# afficheur.net
KiCad netlist of a schematic drawn in Altium Designer
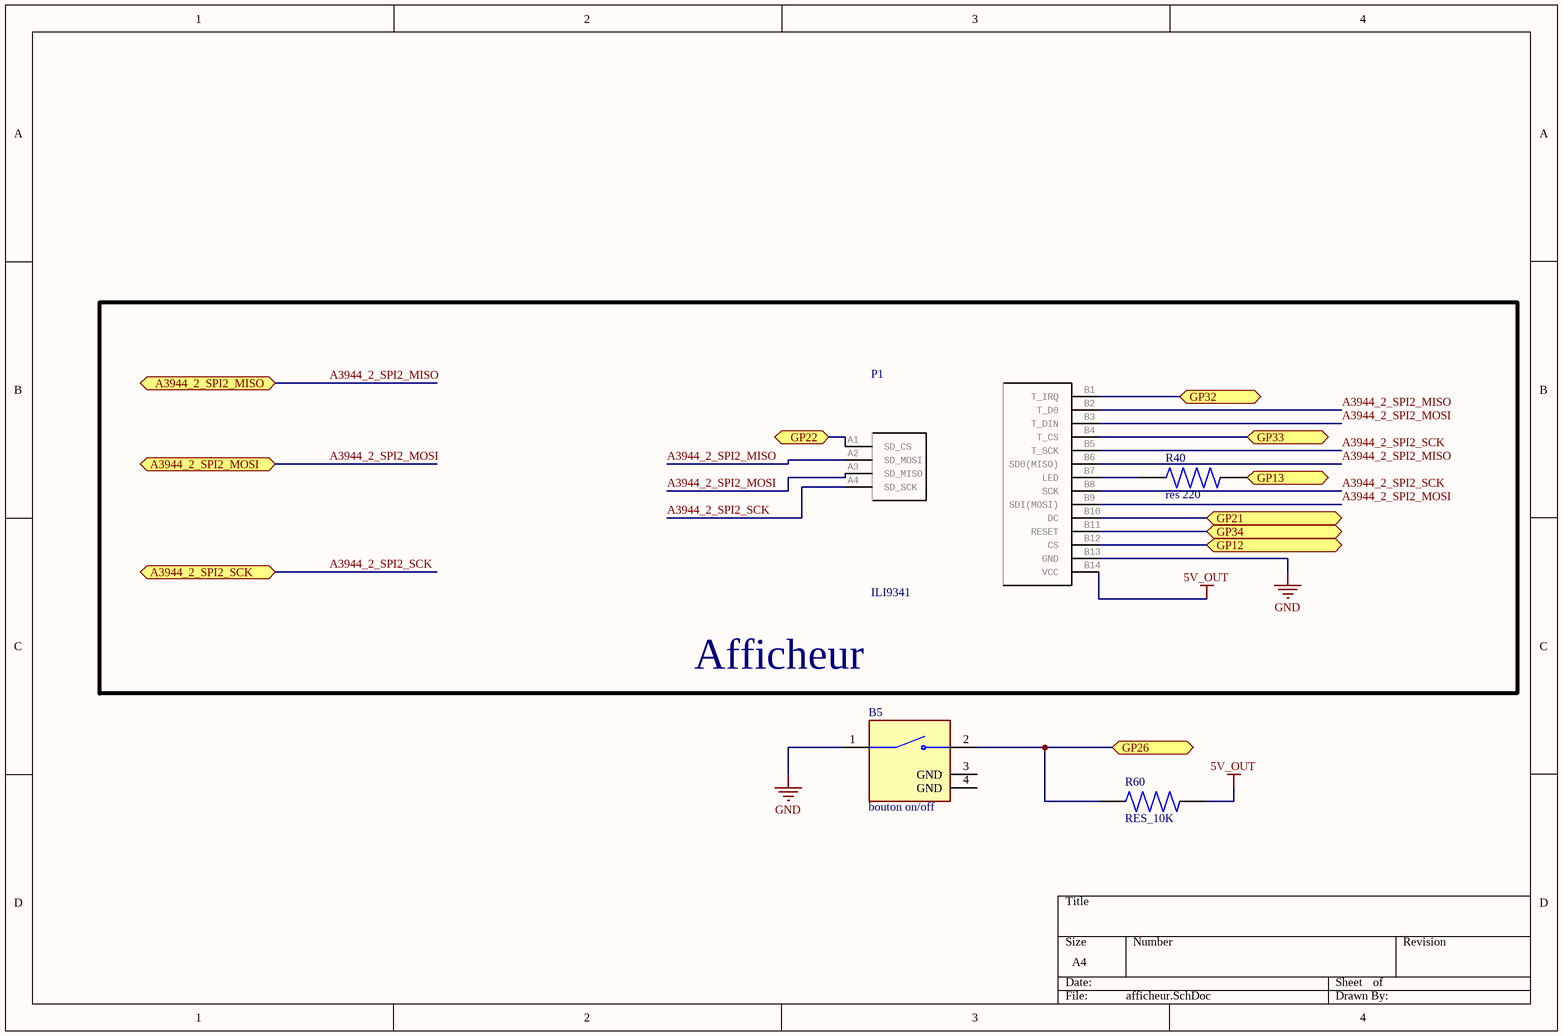
[diagram p0: afficheur.SchDoc]

(export (version "E")
  (design (tool "Eeschema 10.0.6"))
  (components
    (comp (ref "B5")
      (value "bouton on/off")
      (footprint "button")
      (fields (field (name "MFR") "CUI Devices"))
      (libsource (lib "Data_logger") (part "bouton reset"))
    )
    (comp (ref "P1") (value "ILI9341") (footprint "ILI9341") (libsource (lib "Data_logger") (part "ILI9341")))
    (comp (ref "R40")
      (value "res 220")
      (footprint "res 220")
      (libsource (lib "Data_logger") (part "res 220"))
    )
    (comp (ref "R60")
      (value "RES_10K")
      (footprint "RES_10k")
      (description "Thick Film Resistors - SMD ResHighPowerA 0805 10k 1% 1/2W TC100")
      (fields (field (name "MFR") "Bourns Inc."))
      (libsource (lib "Data_logger") (part "RES_10K"))
    )
  )
  (nets
    (net (code "1") (name "/A3944_2_SPI2_MISO") (class "Default")
      (node (ref "P1") (pin "A2") (pinfunction "SD_MOSI_A2") (pintype "passive"))
      (node (ref "P1") (pin "B2") (pinfunction "T_D0_B2") (pintype "passive"))
      (node (ref "P1") (pin "B6") (pinfunction "SD0(MISO)_B6") (pintype "passive"))
    )
    (net (code "2") (name "/A3944_2_SPI2_MOSI") (class "Default")
      (node (ref "P1") (pin "A3") (pinfunction "SD_MISO_A3") (pintype "passive"))
      (node (ref "P1") (pin "B3") (pinfunction "T_DIN_B3") (pintype "passive"))
      (node (ref "P1") (pin "B9") (pinfunction "SDI(MOSI)_B9") (pintype "passive"))
    )
    (net (code "3") (name "/A3944_2_SPI2_SCK") (class "Default")
      (node (ref "P1") (pin "A4") (pinfunction "SD_SCK_A4") (pintype "passive"))
      (node (ref "P1") (pin "B5") (pinfunction "T_SCK_B5") (pintype "passive"))
      (node (ref "P1") (pin "B8") (pinfunction "SCK_B8") (pintype "passive"))
    )
    (net (code "4") (name "/GP12") (class "Default")
      (node (ref "P1") (pin "B12") (pinfunction "CS_B12") (pintype "passive"))
    )
    (net (code "5") (name "/GP13") (class "Default")
      (node (ref "R40") (pin "2") (pinfunction "2_2") (pintype "passive"))
    )
    (net (code "6") (name "/GP21") (class "Default")
      (node (ref "P1") (pin "B10") (pinfunction "DC_B10") (pintype "passive"))
    )
    (net (code "7") (name "/GP22") (class "Default")
      (node (ref "P1") (pin "A1") (pinfunction "SD_CS_A1") (pintype "passive"))
    )
    (net (code "8") (name "/GP26") (class "Default")
      (node (ref "B5") (pin "2") (pinfunction "NO_2") (pintype "passive"))
      (node (ref "R60") (pin "1") (pinfunction "1_1") (pintype "passive"))
    )
    (net (code "9") (name "/GP32") (class "Default")
      (node (ref "P1") (pin "B1") (pinfunction "T_IRQ_B1") (pintype "passive"))
    )
    (net (code "10") (name "/GP33") (class "Default")
      (node (ref "P1") (pin "B4") (pinfunction "T_CS_B4") (pintype "passive"))
    )
    (net (code "11") (name "/GP34") (class "Default")
      (node (ref "P1") (pin "B11") (pinfunction "RESET_B11") (pintype "passive"))
    )
    (net (code "12") (name "5V_OUT") (class "Default")
      (node (ref "P1") (pin "B14") (pinfunction "VCC_B14") (pintype "passive"))
      (node (ref "R60") (pin "2") (pinfunction "2_2") (pintype "passive"))
    )
    (net (code "13") (name "GND") (class "Default")
      (node (ref "B5") (pin "1") (pinfunction "COM_1") (pintype "passive"))
      (node (ref "P1") (pin "B13") (pinfunction "GND_B13") (pintype "passive"))
    )
    (net (code "14") (name "Net-(P1-LED)") (class "Default")
      (node (ref "P1") (pin "B7") (pinfunction "LED_B7") (pintype "passive"))
      (node (ref "R40") (pin "1") (pinfunction "1_1") (pintype "passive"))
    )
    (net (code "15") (name "unconnected-(B5-GND-Pad3)") (class "Default")
      (node (ref "B5") (pin "3") (pinfunction "GND_3") (pintype "power_in"))
    )
    (net (code "16") (name "unconnected-(B5-GND-Pad4)") (class "Default")
      (node (ref "B5") (pin "4") (pinfunction "GND_4") (pintype "power_in"))
    )
  )
)
